# Sheet1.net
KiCad netlist of a schematic drawn in Altium Designer
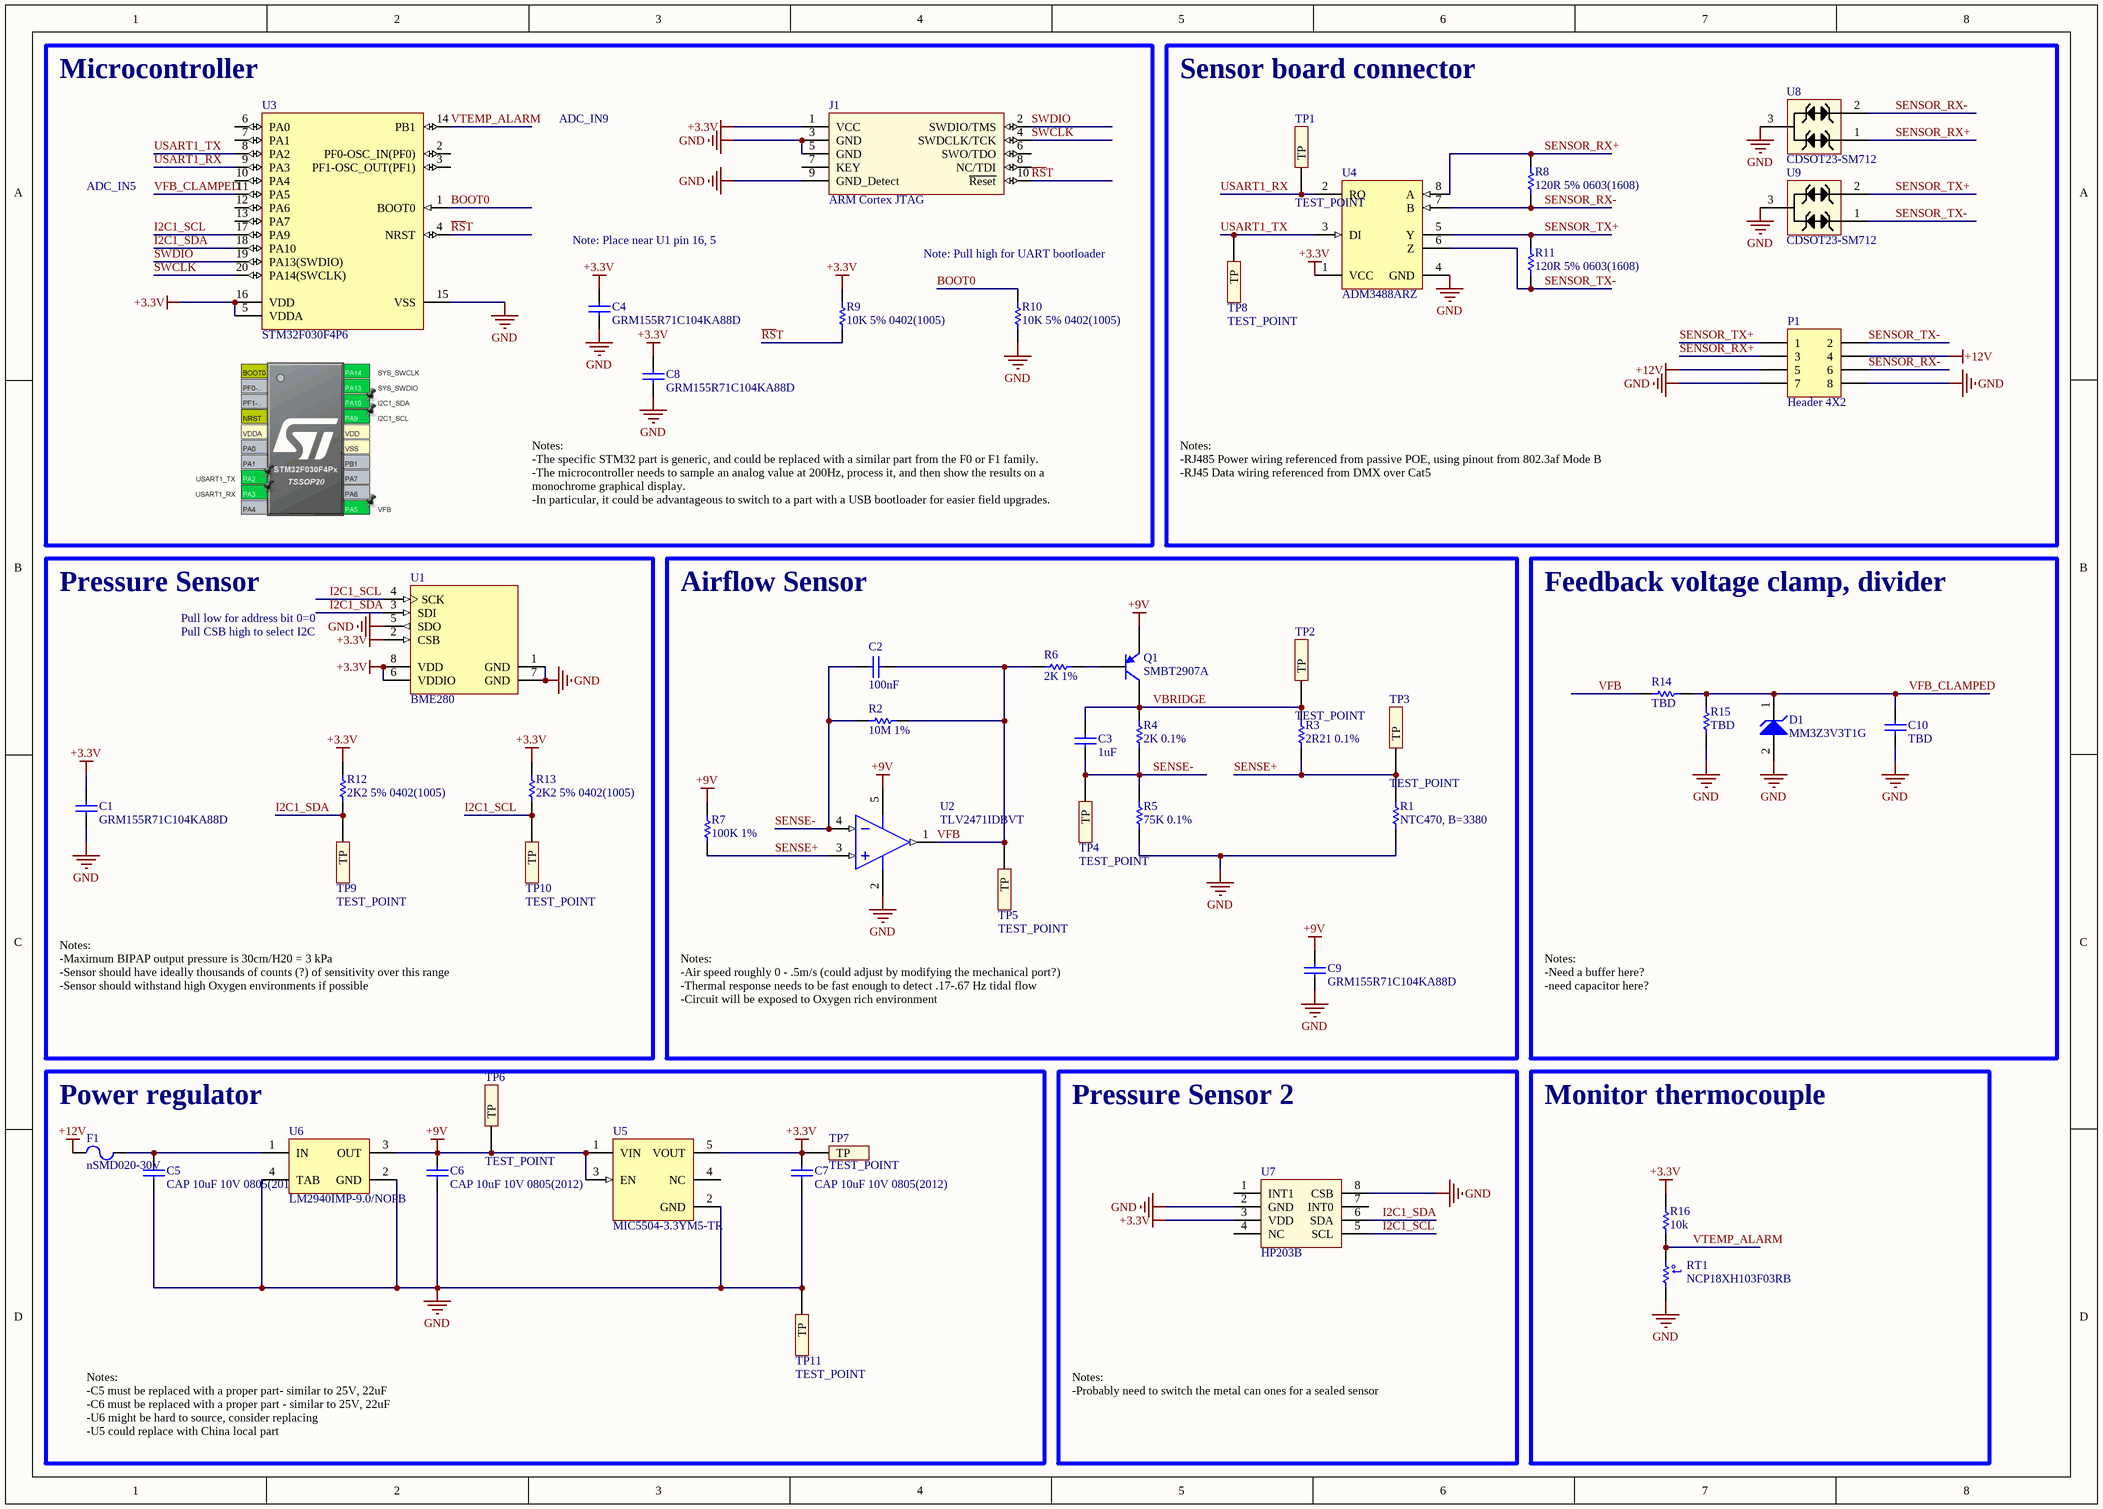
[diagram p0: Sheet1.SchDoc]

(export (version "E")
  (design (tool "Eeschema 10.0.6"))
  (components
    (comp (ref "C1")
      (value "GRM155R71C104KA88D")
      (footprint "CAPC1005X55X25ML05T10")
      (description "Chip Capacitor, 0.1 uF, +/- 10%, 16 V, -55 to 125 degC, 0402 (1005 Metric), RoHS, Tape and Reel")
      (fields (field (name "VOLTAGE") "16V") (field (name "TOLERANCE") "10%"))
      (libsource (lib "Altium Content Vault") (part "CAP-NP-2"))
    )
    (comp (ref "C2")
      (value "100nF")
      (footprint "CAPC1005X55X25ML05T10")
      (description "Chip Capacitor, 0.1 uF, +/- 10%, 16 V, -55 to 125 degC, 0402 (1005 Metric), RoHS, Tape and Reel")
      (fields (field (name "VOLTAGE") "16V") (field (name "TOLERANCE") "10%"))
      (libsource (lib "Altium Content Vault") (part "CAP-NP-2"))
    )
    (comp (ref "C3")
      (value "1uF")
      (footprint "CAPC1005X55X25ML05T10")
      (description "Chip Capacitor, 0.1 uF, +/- 10%, 16 V, -55 to 125 degC, 0402 (1005 Metric), RoHS, Tape and Reel")
      (fields (field (name "VOLTAGE") "16V") (field (name "TOLERANCE") "10%"))
      (libsource (lib "Altium Content Vault") (part "CAP-NP-2"))
    )
    (comp (ref "C4")
      (value "GRM155R71C104KA88D")
      (footprint "CAPC1005X55X25ML05T10")
      (description "Chip Capacitor, 0.1 uF, +/- 10%, 16 V, -55 to 125 degC, 0402 (1005 Metric), RoHS, Tape and Reel")
      (fields (field (name "VOLTAGE") "16V") (field (name "TOLERANCE") "10%"))
      (libsource (lib "Altium Content Vault") (part "CAP-NP-2"))
    )
    (comp (ref "C5")
      (value "CAP 10uF 10V 0805(2012)")
      (footprint "CAPC0805(2012)145_N")
      (description "CAP 10uF 10V ±10% 0805 (2012 Metric) Thickness 1.45mm SMD")
      (fields (field (name "TOLERANCE") "Â±10%"))
      (libsource (lib "Altium Content Vault") (part "CAP"))
    )
    (comp (ref "C6")
      (value "CAP 10uF 10V 0805(2012)")
      (footprint "CAPC0805(2012)145_N")
      (description "CAP 10uF 10V ±10% 0805 (2012 Metric) Thickness 1.45mm SMD")
      (fields (field (name "TOLERANCE") "Â±10%"))
      (libsource (lib "Altium Content Vault") (part "CAP"))
    )
    (comp (ref "C7")
      (value "CAP 10uF 10V 0805(2012)")
      (footprint "CAPC0805(2012)145_N")
      (description "CAP 10uF 10V ±10% 0805 (2012 Metric) Thickness 1.45mm SMD")
      (fields (field (name "TOLERANCE") "Â±10%"))
      (libsource (lib "Altium Content Vault") (part "CAP"))
    )
    (comp (ref "C8")
      (value "GRM155R71C104KA88D")
      (footprint "CAPC1005X55X25ML05T10")
      (description "Chip Capacitor, 0.1 uF, +/- 10%, 16 V, -55 to 125 degC, 0402 (1005 Metric), RoHS, Tape and Reel")
      (fields (field (name "VOLTAGE") "16V") (field (name "TOLERANCE") "10%"))
      (libsource (lib "Altium Content Vault") (part "CAP-NP-2"))
    )
    (comp (ref "C9")
      (value "GRM155R71C104KA88D")
      (footprint "CAPC1005X55X25ML05T10")
      (description "Chip Capacitor, 0.1 uF, +/- 10%, 16 V, -55 to 125 degC, 0402 (1005 Metric), RoHS, Tape and Reel")
      (fields (field (name "VOLTAGE") "16V") (field (name "TOLERANCE") "10%"))
      (libsource (lib "Altium Content Vault") (part "CAP-NP-2"))
    )
    (comp (ref "C10")
      (value "TBD")
      (footprint "CAPC1005X55X25ML05T10")
      (description "Chip Capacitor, 0.1 uF, +/- 10%, 16 V, -55 to 125 degC, 0402 (1005 Metric), RoHS, Tape and Reel")
      (fields (field (name "VOLTAGE") "16V") (field (name "TOLERANCE") "10%"))
      (libsource (lib "Altium Content Vault") (part "CAP-NP-2"))
    )
    (comp (ref "D1")
      (value "MM3Z3V3T1G")
      (footprint "ONSC-SOD-323-2-477-02_V")
      (description "Zener Voltage Regulator, 300 mW, 2-Pin SOD-323, Pb-Free, Tape and Reel")
      (fields (field (name "MANUFACTURER") "On Semiconductor"))
      (libsource (lib "Altium Content Vault") (part "ONSC-K1A2-2"))
    )
    (comp (ref "F1")
      (value "nSMD020-30V")
      (footprint "SEAANDLAND_1206")
      (description "Surface Mount Fuses 30V 100A 200mA 460mA 1206 RoHS")
      (fields
        (field (name "MANUFACTURER") "Sea & Land Electronic Corp")
        (field (name "PARTNUMBER") "NSMD020-30V")
      )
      (libsource (lib "Blinkinlabs") (part "nSMD020-30V"))
    )
    (comp (ref "J1")
      (value "ARM Cortex JTAG")
      (footprint "1.27mm 2x5 SMD Header - no paste")
      (description "Arm Cortex 10-pin JTAG connector")
      (fields (field (name "MANUFACTURER") "Unknown/Generic") (field (name "PARTNUMBER") "unknown/Generic"))
      (libsource (lib "Blinkinlabs") (part "ARM Cortex JTAG"))
    )
    (comp (ref "P1")
      (value "Header 4X2")
      (footprint "HDR2X4")
      (description "Header, 4-Pin, Dual row")
      (fields (field (name "PUBLISHER") "Altium Limited"))
      (libsource (lib "Miscellaneous Connectors") (part "Header 4X2"))
    )
    (comp (ref "Q1")
      (value "SMBT2907A")
      (footprint "INF-SOT23_N")
      (description "PNP Silicon Switching Transistor, 60 V VCEO, 600 mA IC, SOT23, Reel, Green")
      (fields (field (name "MANUFACTURER") "Infineon"))
      (libsource (lib "Altium Content Vault") (part "INF-BJTPNP-BEC-3"))
    )
    (comp (ref "R1")
      (value "NTC470, B=3380")
      (footprint "RESC1005X40X25NL05T05")
      (fields (field (name "MANUFACTURER") "Panasonic") (field (name "PART NUMBER") "ERT-J0EV474J"))
      (libsource (lib "Altium Content Vault") (part "RES"))
    )
    (comp (ref "R2")
      (value "10M 1%")
      (footprint "RESC1005X40X25ML05T10")
      (fields (field (name "PART NUMBER") "RC0402FR-071KL") (field (name "MANUFACTURER") "Yageo / Phycomp"))
      (libsource (lib "Altium Content Vault") (part "RES"))
    )
    (comp (ref "R3")
      (value "2R21 0.1%")
      (footprint "RESC1005X40X25ML05T10")
      (fields (field (name "PART NUMBER") "RC0402FR-071KL") (field (name "MANUFACTURER") "Yageo / Phycomp"))
      (libsource (lib "Altium Content Vault") (part "RES"))
    )
    (comp (ref "R4")
      (value "2K 0.1%")
      (footprint "RESC1005X40X25ML05T10")
      (fields (field (name "PART NUMBER") "RC0402FR-071KL") (field (name "MANUFACTURER") "Yageo / Phycomp"))
      (libsource (lib "Altium Content Vault") (part "RES"))
    )
    (comp (ref "R5")
      (value "75K 0.1%")
      (footprint "RESC1005X40X25ML05T10")
      (fields (field (name "PART NUMBER") "RC0402FR-071KL") (field (name "MANUFACTURER") "Yageo / Phycomp"))
      (libsource (lib "Altium Content Vault") (part "RES"))
    )
    (comp (ref "R6")
      (value "2K 1%")
      (footprint "RESC1005X40X25NL05T05")
      (fields (field (name "MANUFACTURER") "Panasonic") (field (name "PART NUMBER") "ERT-J0EV474J"))
      (libsource (lib "Altium Content Vault") (part "RES"))
    )
    (comp (ref "R7")
      (value "100K 1%")
      (footprint "RESC1005X40X25ML05T10")
      (fields (field (name "PART NUMBER") "RC0402FR-071KL") (field (name "MANUFACTURER") "Yageo / Phycomp"))
      (libsource (lib "Altium Content Vault") (part "RES"))
    )
    (comp (ref "R8")
      (value "120R 5% 0603(1608)")
      (footprint "RESC0603(1608)_L")
      (description "120R 0.1W 5% 0603 (1608 Metric)  SMD")
      (fields (field (name "POWER") "0.1 W") (field (name "TOLERANCE") "5 %"))
      (libsource (lib "Altium Content Vault") (part "RES"))
    )
    (comp (ref "R9")
      (value "10K 5% 0402(1005)")
      (footprint "RESC0402(1005)_N")
      (description "10K 0.063W 5% 0402 (1005 Metric)  SMD")
      (fields (field (name "TOLERANCE") "5 %") (field (name "POWER") "0.063 W"))
      (libsource (lib "Altium Content Vault") (part "RES"))
    )
    (comp (ref "R10")
      (value "10K 5% 0402(1005)")
      (footprint "RESC0402(1005)_N")
      (description "10K 0.063W 5% 0402 (1005 Metric)  SMD")
      (fields (field (name "TOLERANCE") "5 %") (field (name "POWER") "0.063 W"))
      (libsource (lib "Altium Content Vault") (part "RES"))
    )
    (comp (ref "R11")
      (value "120R 5% 0603(1608)")
      (footprint "RESC0603(1608)_L")
      (description "120R 0.1W 5% 0603 (1608 Metric)  SMD")
      (fields (field (name "POWER") "0.1 W") (field (name "TOLERANCE") "5 %"))
      (libsource (lib "Altium Content Vault") (part "RES"))
    )
    (comp (ref "R12")
      (value "2K2 5% 0402(1005)")
      (footprint "RESC0402(1005)_N")
      (description "2K2 0.063W 5% 0402 (1005 Metric)  SMD")
      (fields (field (name "TOLERANCE") "5 %") (field (name "POWER") "0.063 W"))
      (libsource (lib "Altium Content Vault") (part "RES"))
    )
    (comp (ref "R13")
      (value "2K2 5% 0402(1005)")
      (footprint "RESC0402(1005)_N")
      (description "2K2 0.063W 5% 0402 (1005 Metric)  SMD")
      (fields (field (name "TOLERANCE") "5 %") (field (name "POWER") "0.063 W"))
      (libsource (lib "Altium Content Vault") (part "RES"))
    )
    (comp (ref "R14")
      (value "TBD")
      (footprint "RESC1005X40X25ML05T10")
      (fields (field (name "PART NUMBER") "RC0402FR-071KL") (field (name "MANUFACTURER") "Yageo / Phycomp"))
      (libsource (lib "Altium Content Vault") (part "RES"))
    )
    (comp (ref "R15")
      (value "TBD")
      (footprint "RESC1005X40X25ML05T10")
      (fields (field (name "PART NUMBER") "RC0402FR-071KL") (field (name "MANUFACTURER") "Yageo / Phycomp"))
      (libsource (lib "Altium Content Vault") (part "RES"))
    )
    (comp (ref "R16")
      (value "10k")
      (footprint "RESC1005X40X25ML05T10")
      (fields (field (name "PART NUMBER") "RC0402FR-071KL") (field (name "MANUFACTURER") "Yageo / Phycomp"))
      (libsource (lib "Altium Content Vault") (part "RES"))
    )
    (comp (ref "RT1")
      (value "NCP18XH103F03RB")
      (footprint "MURA-NCP18XH103F03RB-2_V")
      (description "NTC Thermistor, 10 KOhm, +/- 1%, 0.1 W, -40 to 125 degC, 0603 (1608 Metric), RoHS, Tape and Reel")
      (fields (field (name "MANUFACTURER") "Murata"))
      (libsource (lib "Altium Content Vault") (part "MURA-NCP18XH103F03RB-2"))
    )
    (comp (ref "TP1")
      (value "TEST_POINT")
      (footprint "TP-SMD-1mm")
      (description "Test point")
      (libsource (lib "") (part "TEST_POINT_1"))
    )
    (comp (ref "TP2")
      (value "TEST_POINT")
      (footprint "TP-SMD-1mm")
      (description "Test point")
      (libsource (lib "") (part "TEST_POINT_1"))
    )
    (comp (ref "TP3")
      (value "TEST_POINT")
      (footprint "TP-SMD-1mm")
      (description "Test point")
      (libsource (lib "") (part "TEST_POINT_1"))
    )
    (comp (ref "TP4")
      (value "TEST_POINT")
      (footprint "TP-SMD-1mm")
      (description "Test point")
      (libsource (lib "Blinkinlabs") (part "TEST_POINT"))
    )
    (comp (ref "TP5")
      (value "TEST_POINT")
      (footprint "TP-SMD-1mm")
      (description "Test point")
      (libsource (lib "Blinkinlabs") (part "TEST_POINT"))
    )
    (comp (ref "TP6")
      (value "TEST_POINT")
      (footprint "TP-SMD-1mm")
      (description "Test point")
      (libsource (lib "") (part "TEST_POINT_1"))
    )
    (comp (ref "TP7")
      (value "TEST_POINT")
      (footprint "TP-SMD-1mm")
      (description "Test point")
      (libsource (lib "") (part "TEST_POINT_2"))
    )
    (comp (ref "TP8")
      (value "TEST_POINT")
      (footprint "TP-SMD-1mm")
      (description "Test point")
      (libsource (lib "Blinkinlabs") (part "TEST_POINT"))
    )
    (comp (ref "TP9")
      (value "TEST_POINT")
      (footprint "TP-SMD-1mm")
      (description "Test point")
      (libsource (lib "Blinkinlabs") (part "TEST_POINT"))
    )
    (comp (ref "TP10")
      (value "TEST_POINT")
      (footprint "TP-SMD-1mm")
      (description "Test point")
      (libsource (lib "Blinkinlabs") (part "TEST_POINT"))
    )
    (comp (ref "TP11")
      (value "TEST_POINT")
      (footprint "TP-SMD-1mm")
      (description "Test point")
      (libsource (lib "Blinkinlabs") (part "TEST_POINT"))
    )
    (comp (ref "U1")
      (value "BME280")
      (footprint "BOSC-BME280-8_V")
      (fields (field (name "MANUFACTURER") "Bosch Sensortec"))
      (libsource (lib "Altium Content Vault") (part "BOSC-BME280-8"))
    )
    (comp (ref "U2")
      (value "TLV2471IDBVT")
      (footprint "DBV0005A_L")
      (fields (field (name "MANUFACTURER") "Texas Instruments"))
      (libsource (lib "Altium Content Vault") (part "TI-TLV2XX1DBV5"))
    )
    (comp (ref "U3")
      (value "STM32F030F4P6")
      (footprint "STM-TSSOP20_L")
      (libsource (lib "Altium Content Vault") (part "MC-ARM-STM32F030-IL20"))
    )
    (comp (ref "U4")
      (value "ADM3488ARZ")
      (footprint "ADI-R-8_L")
      (fields (field (name "MANUFACTURER") "Analog Devices"))
      (libsource (lib "Altium Content Vault") (part "ADI-ADM3488_90-R-8"))
    )
    (comp (ref "U5")
      (value "MIC5504-3.3YM5-TR")
      (footprint "MCHP-SOT-23-M5_V")
      (fields (field (name "MANUFACTURER") "Microchip"))
      (libsource (lib "Altium Content Vault") (part "MCHP-MIC5504-SOT-23-M5"))
    )
    (comp (ref "U6")
      (value "LM2940IMP-9.0/NOPB")
      (footprint "DCY0004A_L")
      (description "1A Low Dropout Regulator, 4-pin SOT-223, Pb-Free")
      (fields (field (name "MANUFACTURER") "Texas Instruments"))
      (libsource (lib "Altium Content Vault") (part "PM-REG-LM2940-TO4"))
    )
    (comp (ref "U7")
      (value "HP203B")
      (footprint "HP203B")
      (description "PRECISION BAROMETER AND ALTIMETER SENSOR")
      (fields (field (name "MANUFACTURER") "HopeRF"))
      (libsource (lib "Blinkinlabs") (part "HP203B"))
    )
    (comp (ref "U8")
      (value "CDSOT23-SM712")
      (footprint "SOT95P230X117-3N")
      (description "600 WATT TVS ARRAY - ASYMMETRICAL DATA LINE PROTECTOR")
      (fields (field (name "MANUFACTURER") "Bourns"))
      (libsource (lib "Blinkinlabs") (part "CDSOT23-SM712"))
    )
    (comp (ref "U9")
      (value "CDSOT23-SM712")
      (footprint "SOT95P230X117-3N")
      (description "600 WATT TVS ARRAY - ASYMMETRICAL DATA LINE PROTECTOR")
      (fields (field (name "MANUFACTURER") "Bourns"))
      (libsource (lib "Blinkinlabs") (part "CDSOT23-SM712"))
    )
  )
  (nets
    (net (code "1") (name "+3.3V") (class "Default")
      (node (ref "C1") (pin "2") (pinfunction "2_2") (pintype "passive"))
      (node (ref "C4") (pin "2") (pinfunction "2_2") (pintype "passive"))
      (node (ref "C7") (pin "2") (pinfunction "2_2") (pintype "passive"))
      (node (ref "C8") (pin "2") (pinfunction "2_2") (pintype "passive"))
      (node (ref "J1") (pin "1") (pinfunction "VCC_1") (pintype "power_in"))
      (node (ref "R12") (pin "2") (pinfunction "2_2") (pintype "passive"))
      (node (ref "R13") (pin "2") (pinfunction "2_2") (pintype "passive"))
      (node (ref "R16") (pin "1") (pinfunction "1_1") (pintype "passive"))
      (node (ref "R9") (pin "1") (pinfunction "1_1") (pintype "passive"))
      (node (ref "TP7") (pin "1") (pinfunction "TP_1") (pintype "passive"))
      (node (ref "U1") (pin "2") (pinfunction "CSB_2") (pintype "input"))
      (node (ref "U1") (pin "6") (pinfunction "VDDIO_6") (pintype "power_in"))
      (node (ref "U1") (pin "8") (pinfunction "VDD_8") (pintype "power_in"))
      (node (ref "U3") (pin "16") (pinfunction "VDD_16") (pintype "power_in"))
      (node (ref "U3") (pin "5") (pinfunction "VDDA_5") (pintype "power_in"))
      (node (ref "U4") (pin "1") (pinfunction "VCC_1") (pintype "power_in"))
      (node (ref "U5") (pin "5") (pinfunction "VOUT_5") (pintype "power_in"))
      (node (ref "U7") (pin "3") (pinfunction "VDD_3") (pintype "power_in"))
    )
    (net (code "2") (name "+9V") (class "Default")
      (node (ref "C6") (pin "2") (pinfunction "2_2") (pintype "passive"))
      (node (ref "C9") (pin "2") (pinfunction "2_2") (pintype "passive"))
      (node (ref "Q1") (pin "2") (pinfunction "E_2") (pintype "passive"))
      (node (ref "R7") (pin "1") (pinfunction "1_1") (pintype "passive"))
      (node (ref "TP6") (pin "1") (pinfunction "TP_1") (pintype "passive"))
      (node (ref "U2") (pin "5") (pinfunction "VDD_5") (pintype "power_in"))
      (node (ref "U5") (pin "1") (pinfunction "VIN_1") (pintype "power_in"))
      (node (ref "U5") (pin "3") (pinfunction "EN_3") (pintype "input"))
      (node (ref "U6") (pin "3") (pinfunction "OUT_3") (pintype "power_in"))
    )
    (net (code "3") (name "+12V") (class "Default")
      (node (ref "F1") (pin "1") (pinfunction "1_1") (pintype "passive"))
      (node (ref "P1") (pin "4") (pinfunction "4_4") (pintype "passive"))
      (node (ref "P1") (pin "5") (pinfunction "5_5") (pintype "passive"))
    )
    (net (code "4") (name "/BOOT0") (class "Default")
      (node (ref "R10") (pin "1") (pinfunction "1_1") (pintype "passive"))
      (node (ref "U3") (pin "1") (pinfunction "BOOT0_1") (pintype "input"))
    )
    (net (code "5") (name "/I2C1_SCL") (class "Default")
      (node (ref "R13") (pin "1") (pinfunction "1_1") (pintype "passive"))
      (node (ref "TP10") (pin "1") (pinfunction "TP_1") (pintype "passive"))
      (node (ref "U1") (pin "4") (pinfunction "SCK_4") (pintype "input"))
      (node (ref "U3") (pin "17") (pinfunction "PA9_17") (pintype "bidirectional"))
      (node (ref "U7") (pin "5") (pinfunction "SCL_5") (pintype "passive"))
    )
    (net (code "6") (name "/I2C1_SDA") (class "Default")
      (node (ref "R12") (pin "1") (pinfunction "1_1") (pintype "passive"))
      (node (ref "TP9") (pin "1") (pinfunction "TP_1") (pintype "passive"))
      (node (ref "U1") (pin "3") (pinfunction "SDI_3") (pintype "input"))
      (node (ref "U3") (pin "18") (pinfunction "PA10_18") (pintype "bidirectional"))
      (node (ref "U7") (pin "6") (pinfunction "SDA_6") (pintype "passive"))
    )
    (net (code "7") (name "/SENSE+") (class "Default")
      (node (ref "R1") (pin "2") (pinfunction "2_2") (pintype "passive"))
      (node (ref "R3") (pin "1") (pinfunction "1_1") (pintype "passive"))
      (node (ref "R7") (pin "2") (pinfunction "2_2") (pintype "passive"))
      (node (ref "TP3") (pin "1") (pinfunction "TP_1") (pintype "passive"))
      (node (ref "U2") (pin "3") (pinfunction "IN+_3") (pintype "input"))
    )
    (net (code "8") (name "/SENSE-") (class "Default")
      (node (ref "C2") (pin "2") (pinfunction "2_2") (pintype "passive"))
      (node (ref "C3") (pin "2") (pinfunction "2_2") (pintype "passive"))
      (node (ref "R2") (pin "2") (pinfunction "2_2") (pintype "passive"))
      (node (ref "R4") (pin "1") (pinfunction "1_1") (pintype "passive"))
      (node (ref "R5") (pin "2") (pinfunction "2_2") (pintype "passive"))
      (node (ref "TP4") (pin "1") (pinfunction "TP_1") (pintype "passive"))
      (node (ref "U2") (pin "4") (pinfunction "IN-_4") (pintype "input"))
    )
    (net (code "9") (name "/SENSOR_RX+") (class "Default")
      (node (ref "P1") (pin "3") (pinfunction "3_3") (pintype "passive"))
      (node (ref "R8") (pin "2") (pinfunction "2_2") (pintype "passive"))
      (node (ref "U4") (pin "8") (pinfunction "A_8") (pintype "input"))
      (node (ref "U8") (pin "1") (pintype "passive"))
    )
    (net (code "10") (name "/SENSOR_RX-") (class "Default")
      (node (ref "P1") (pin "6") (pinfunction "6_6") (pintype "passive"))
      (node (ref "R8") (pin "1") (pinfunction "1_1") (pintype "passive"))
      (node (ref "U4") (pin "7") (pinfunction "B_7") (pintype "input"))
      (node (ref "U8") (pin "2") (pintype "passive"))
    )
    (net (code "11") (name "/SENSOR_TX+") (class "Default")
      (node (ref "P1") (pin "1") (pinfunction "1_1") (pintype "passive"))
      (node (ref "R11") (pin "2") (pinfunction "2_2") (pintype "passive"))
      (node (ref "U4") (pin "5") (pinfunction "Y_5") (pintype "tri_state"))
      (node (ref "U9") (pin "2") (pintype "passive"))
    )
    (net (code "12") (name "/SENSOR_TX-") (class "Default")
      (node (ref "P1") (pin "2") (pinfunction "2_2") (pintype "passive"))
      (node (ref "R11") (pin "1") (pinfunction "1_1") (pintype "passive"))
      (node (ref "U4") (pin "6") (pinfunction "Z_6") (pintype "tri_state"))
      (node (ref "U9") (pin "1") (pintype "passive"))
    )
    (net (code "13") (name "/SWCLK") (class "Default")
      (node (ref "J1") (pin "4") (pinfunction "SWDCLK/TCK_4") (pintype "bidirectional"))
      (node (ref "U3") (pin "20") (pinfunction "PA14(SWCLK)_20") (pintype "bidirectional"))
    )
    (net (code "14") (name "/SWDIO") (class "Default")
      (node (ref "J1") (pin "2") (pinfunction "SWDIO/TMS_2") (pintype "bidirectional"))
      (node (ref "U3") (pin "19") (pinfunction "PA13(SWDIO)_19") (pintype "bidirectional"))
    )
    (net (code "15") (name "/USART1_RX") (class "Default")
      (node (ref "TP1") (pin "1") (pinfunction "TP_1") (pintype "passive"))
      (node (ref "U3") (pin "9") (pinfunction "PA3_9") (pintype "bidirectional"))
      (node (ref "U4") (pin "2") (pinfunction "RO_2") (pintype "tri_state"))
    )
    (net (code "16") (name "/USART1_TX") (class "Default")
      (node (ref "TP8") (pin "1") (pinfunction "TP_1") (pintype "passive"))
      (node (ref "U3") (pin "8") (pinfunction "PA2_8") (pintype "bidirectional"))
      (node (ref "U4") (pin "3") (pinfunction "DI_3") (pintype "input"))
    )
    (net (code "17") (name "/VBRIDGE") (class "Default")
      (node (ref "C3") (pin "1") (pinfunction "1_1") (pintype "passive"))
      (node (ref "Q1") (pin "3") (pinfunction "C_3") (pintype "passive"))
      (node (ref "R3") (pin "2") (pinfunction "2_2") (pintype "passive"))
      (node (ref "R4") (pin "2") (pinfunction "2_2") (pintype "passive"))
      (node (ref "TP2") (pin "1") (pinfunction "TP_1") (pintype "passive"))
    )
    (net (code "18") (name "/VFB") (class "Default")
      (node (ref "C2") (pin "1") (pinfunction "1_1") (pintype "passive"))
      (node (ref "R14") (pin "2") (pinfunction "2_2") (pintype "passive"))
      (node (ref "R2") (pin "1") (pinfunction "1_1") (pintype "passive"))
      (node (ref "R6") (pin "2") (pinfunction "2_2") (pintype "passive"))
      (node (ref "TP5") (pin "1") (pinfunction "TP_1") (pintype "passive"))
      (node (ref "U2") (pin "1") (pinfunction "OUT_1") (pintype "output"))
    )
    (net (code "19") (name "/VFB_CLAMPED") (class "Default")
      (node (ref "C10") (pin "1") (pinfunction "1_1") (pintype "passive"))
      (node (ref "D1") (pin "1") (pinfunction "K_1") (pintype "passive"))
      (node (ref "R14") (pin "1") (pinfunction "1_1") (pintype "passive"))
      (node (ref "R15") (pin "1") (pinfunction "1_1") (pintype "passive"))
      (node (ref "U3") (pin "11") (pinfunction "PA5_11") (pintype "bidirectional"))
    )
    (net (code "20") (name "/VTEMP_ALARM") (class "Default")
      (node (ref "R16") (pin "2") (pinfunction "2_2") (pintype "passive"))
      (node (ref "RT1") (pin "2") (pinfunction "2_2") (pintype "passive"))
      (node (ref "U3") (pin "14") (pinfunction "PB1_14") (pintype "bidirectional"))
    )
    (net (code "21") (name "/~{RS}T") (class "Default")
      (node (ref "J1") (pin "10") (pinfunction "~{Reset}_10") (pintype "bidirectional"))
      (node (ref "R9") (pin "2") (pinfunction "2_2") (pintype "passive"))
      (node (ref "U3") (pin "4") (pinfunction "NRST_4") (pintype "bidirectional"))
    )
    (net (code "22") (name "GND") (class "Default")
      (node (ref "C1") (pin "1") (pinfunction "1_1") (pintype "passive"))
      (node (ref "C10") (pin "2") (pinfunction "2_2") (pintype "passive"))
      (node (ref "C4") (pin "1") (pinfunction "1_1") (pintype "passive"))
      (node (ref "C5") (pin "1") (pinfunction "1_1") (pintype "passive"))
      (node (ref "C6") (pin "1") (pinfunction "1_1") (pintype "passive"))
      (node (ref "C7") (pin "1") (pinfunction "1_1") (pintype "passive"))
      (node (ref "C8") (pin "1") (pinfunction "1_1") (pintype "passive"))
      (node (ref "C9") (pin "1") (pinfunction "1_1") (pintype "passive"))
      (node (ref "D1") (pin "2") (pinfunction "A_2") (pintype "passive"))
      (node (ref "J1") (pin "3") (pinfunction "GND_3") (pintype "power_in"))
      (node (ref "J1") (pin "5") (pinfunction "GND_5") (pintype "power_in"))
      (node (ref "J1") (pin "9") (pinfunction "GND_Detect_9") (pintype "power_in"))
      (node (ref "P1") (pin "7") (pinfunction "7_7") (pintype "passive"))
      (node (ref "P1") (pin "8") (pinfunction "8_8") (pintype "passive"))
      (node (ref "R1") (pin "1") (pinfunction "1_1") (pintype "passive"))
      (node (ref "R10") (pin "2") (pinfunction "2_2") (pintype "passive"))
      (node (ref "R15") (pin "2") (pinfunction "2_2") (pintype "passive"))
      (node (ref "R5") (pin "1") (pinfunction "1_1") (pintype "passive"))
      (node (ref "RT1") (pin "1") (pinfunction "1_1") (pintype "passive"))
      (node (ref "TP11") (pin "1") (pinfunction "TP_1") (pintype "passive"))
      (node (ref "U1") (pin "1") (pinfunction "GND_1") (pintype "power_in"))
      (node (ref "U1") (pin "5") (pinfunction "SDO_5") (pintype "output"))
      (node (ref "U1") (pin "7") (pinfunction "GND_7") (pintype "power_in"))
      (node (ref "U2") (pin "2") (pinfunction "GND_2") (pintype "power_in"))
      (node (ref "U3") (pin "15") (pinfunction "VSS_15") (pintype "power_in"))
      (node (ref "U4") (pin "4") (pinfunction "GND_4") (pintype "power_in"))
      (node (ref "U5") (pin "2") (pinfunction "GND_2") (pintype "power_in"))
      (node (ref "U6") (pin "2") (pinfunction "GND_2") (pintype "power_in"))
      (node (ref "U6") (pin "4") (pinfunction "TAB_4") (pintype "power_in"))
      (node (ref "U7") (pin "2") (pinfunction "GND_2") (pintype "power_in"))
      (node (ref "U7") (pin "8") (pinfunction "CSB_8") (pintype "passive"))
      (node (ref "U8") (pin "3") (pintype "passive"))
      (node (ref "U9") (pin "3") (pintype "passive"))
    )
    (net (code "23") (name "Net-(Q1-B)") (class "Default")
      (node (ref "Q1") (pin "1") (pinfunction "B_1") (pintype "passive"))
      (node (ref "R6") (pin "1") (pinfunction "1_1") (pintype "passive"))
    )
    (net (code "24") (name "Net-(U6-IN)") (class "Default")
      (node (ref "C5") (pin "2") (pinfunction "2_2") (pintype "passive"))
      (node (ref "F1") (pin "2") (pinfunction "2_2") (pintype "passive"))
      (node (ref "U6") (pin "1") (pinfunction "IN_1") (pintype "power_in"))
    )
    (net (code "25") (name "unconnected-(J1-KEY-Pad7)") (class "Default")
      (node (ref "J1") (pin "7") (pinfunction "KEY_7") (pintype "passive"))
    )
    (net (code "26") (name "unconnected-(J1-NC{slash}TDI-Pad8)") (class "Default")
      (node (ref "J1") (pin "8") (pinfunction "NC/TDI_8") (pintype "bidirectional"))
    )
    (net (code "27") (name "unconnected-(J1-SWO{slash}TDO-Pad6)") (class "Default")
      (node (ref "J1") (pin "6") (pinfunction "SWO/TDO_6") (pintype "bidirectional"))
    )
    (net (code "28") (name "unconnected-(U3-PA0-Pad6)") (class "Default")
      (node (ref "U3") (pin "6") (pinfunction "PA0_6") (pintype "bidirectional"))
    )
    (net (code "29") (name "unconnected-(U3-PA1-Pad7)") (class "Default")
      (node (ref "U3") (pin "7") (pinfunction "PA1_7") (pintype "bidirectional"))
    )
    (net (code "30") (name "unconnected-(U3-PA4-Pad10)") (class "Default")
      (node (ref "U3") (pin "10") (pinfunction "PA4_10") (pintype "bidirectional"))
    )
    (net (code "31") (name "unconnected-(U3-PA6-Pad12)") (class "Default")
      (node (ref "U3") (pin "12") (pinfunction "PA6_12") (pintype "bidirectional"))
    )
    (net (code "32") (name "unconnected-(U3-PA7-Pad13)") (class "Default")
      (node (ref "U3") (pin "13") (pinfunction "PA7_13") (pintype "bidirectional"))
    )
    (net (code "33") (name "unconnected-(U3-PF0-OSC_IN(PF0)-Pad2)") (class "Default")
      (node (ref "U3") (pin "2") (pinfunction "PF0-OSC_IN(PF0)_2") (pintype "bidirectional"))
    )
    (net (code "34") (name "unconnected-(U3-PF1-OSC_OUT(PF1)-Pad3)") (class "Default")
      (node (ref "U3") (pin "3") (pinfunction "PF1-OSC_OUT(PF1)_3") (pintype "bidirectional"))
    )
    (net (code "35") (name "unconnected-(U5-NC-Pad4)") (class "Default")
      (node (ref "U5") (pin "4") (pinfunction "NC_4") (pintype "passive"))
    )
    (net (code "36") (name "unconnected-(U7-INT0-Pad7)") (class "Default")
      (node (ref "U7") (pin "7") (pinfunction "INT0_7") (pintype "passive"))
    )
    (net (code "37") (name "unconnected-(U7-INT1-Pad1)") (class "Default")
      (node (ref "U7") (pin "1") (pinfunction "INT1_1") (pintype "passive"))
    )
    (net (code "38") (name "unconnected-(U7-NC-Pad4)") (class "Default")
      (node (ref "U7") (pin "4") (pinfunction "NC_4") (pintype "passive"))
    )
  )
)
